# Capybara.net
KiCad netlist of a schematic drawn in Altium Designer
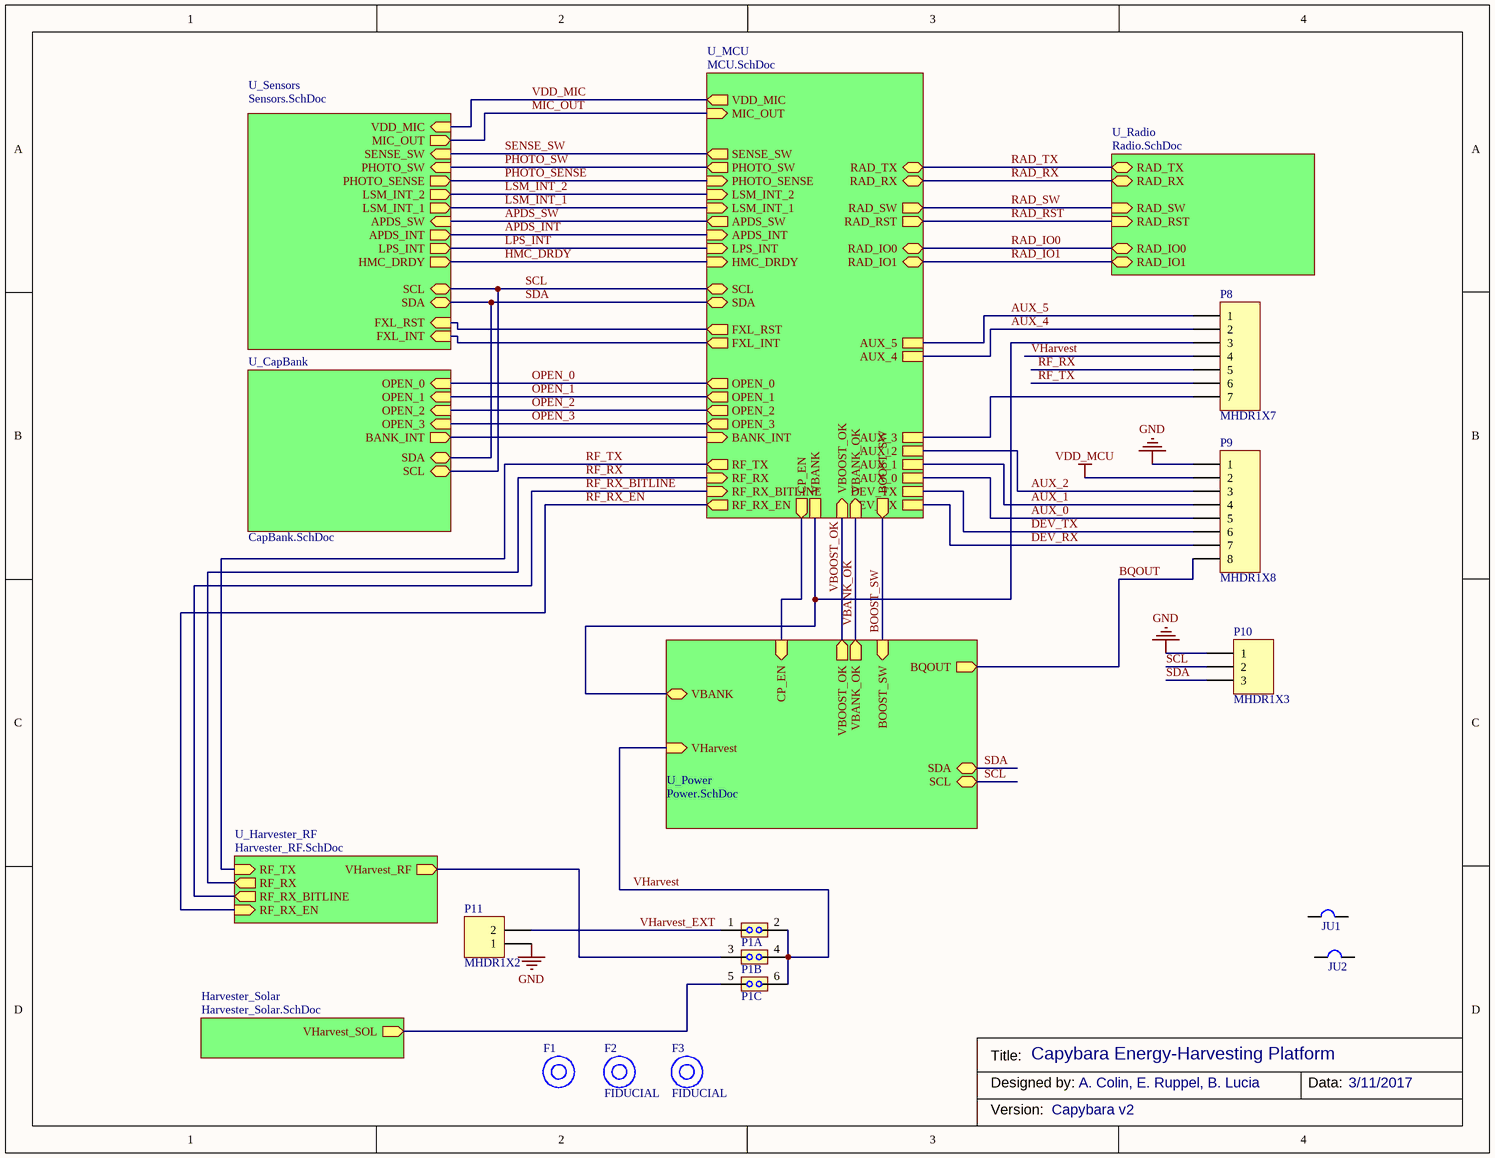
[diagram p0: Capybara.SchDoc]

(export (version "E")
  (design (tool "Eeschema 10.0.6"))
  (components
    (comp (ref "F1") (value "FIDUCIAL") (footprint "FIDUCIAL") (libsource (lib "Sprite") (part "FIDUCIAL")))
    (comp (ref "F2") (value "FIDUCIAL") (footprint "FIDUCIAL") (libsource (lib "Sprite") (part "FIDUCIAL")))
    (comp (ref "F3") (value "FIDUCIAL") (footprint "FIDUCIAL") (libsource (lib "Sprite") (part "FIDUCIAL")))
    (comp (ref "JU1") (value "JUMPER") (footprint "JUMPER0603") (libsource (lib "Sprite") (part "JUMPER")))
    (comp (ref "JU2") (value "JUMPER") (footprint "JUMPER0603") (libsource (lib "Sprite") (part "JUMPER")))
    (comp (ref "P1")
      (value "JMPHDR_12")
      (footprint "MHDR2X12")
      (fields
        (field (name "DIGI-KEY PART NUMBER") "S9015E-12-ND")
        (field (name "MANUFACTURER") "Sullins Connector Solutions")
        (field (name "MANUFACTURER PART NUMBER") "GRPB122VWVN-RC")
      )
      (libsource (lib "Sprite") (part "JMPHDR_12"))
    )
    (comp (ref "P8")
      (value "MHDR1X7")
      (footprint "MHDR1X7")
      (description "Header, 7-Pin")
      (fields
        (field (name "DIGI-KEY PART NUMBER") "952-3360-ND")
        (field (name "DISTRIBUTOR PART NUMBER") "855-M52-5000745")
        (field (name "PUBLISHER") "Altium Limited")
      )
      (libsource (lib "Miscellaneous Connectors") (part "MHDR1X7"))
    )
    (comp (ref "P9")
      (value "MHDR1X8")
      (footprint "MHDR1X8")
      (description "Header, 8-Pin")
      (fields
        (field (name "DIGI-KEY PART NUMBER") "952-3361-ND")
        (field (name "DISTRIBUTOR PART NUMBER") "855-M52-5000845")
        (field (name "PUBLISHER") "Altium Limited")
      )
      (libsource (lib "Miscellaneous Connectors") (part "MHDR1X8"))
    )
    (comp (ref "P10")
      (value "MHDR1X3")
      (footprint "MHDR1X3")
      (description "Header, 3-Pin")
      (fields
        (field (name "DIGI-KEY PART NUMBER") "952-3357-ND")
        (field (name "DISTRIBUTOR PART NUMBER") "855-M52-5000345")
        (field (name "PUBLISHER") "Altium Limited")
      )
      (libsource (lib "Miscellaneous Connectors") (part "MHDR1X3"))
    )
    (comp (ref "P11")
      (value "MHDR1X2")
      (footprint "MHDR1X2")
      (description "Header, 2-Pin")
      (fields
        (field (name "DIGI-KEY PART NUMBER") "SAM9931-ND")
        (field (name "MANUFACTURER") "Samtec Inc.")
        (field (name "PUBLISHER") "Altium Limited")
      )
      (libsource (lib "Miscellaneous Connectors") (part "MHDR1X2"))
    )
  )
  (nets
    (net (code "3") (name "/AUX_0") (class "Default")
      (node (ref "P9") (pin "5") (pinfunction "5_5") (pintype "passive"))
    )
    (net (code "4") (name "/AUX_1") (class "Default")
      (node (ref "P9") (pin "4") (pinfunction "4_4") (pintype "passive"))
    )
    (net (code "5") (name "/AUX_2") (class "Default")
      (node (ref "P9") (pin "3") (pinfunction "3_3") (pintype "passive"))
    )
    (net (code "6") (name "/AUX_3") (class "Default")
      (node (ref "P8") (pin "7") (pinfunction "7_7") (pintype "passive"))
    )
    (net (code "7") (name "/AUX_4") (class "Default")
      (node (ref "P8") (pin "2") (pinfunction "2_2") (pintype "passive"))
    )
    (net (code "8") (name "/AUX_5") (class "Default")
      (node (ref "P8") (pin "1") (pinfunction "1_1") (pintype "passive"))
    )
    (net (code "11") (name "/BQOUT") (class "Default")
      (node (ref "P9") (pin "8") (pinfunction "8_8") (pintype "passive"))
    )
    (net (code "13") (name "/DEV_RX") (class "Default")
      (node (ref "P9") (pin "7") (pinfunction "7_7") (pintype "passive"))
    )
    (net (code "14") (name "/DEV_TX") (class "Default")
      (node (ref "P9") (pin "6") (pinfunction "6_6") (pintype "passive"))
    )
    (net (code "34") (name "/RF_RX") (class "Default")
      (node (ref "P8") (pin "5") (pinfunction "5_5") (pintype "passive"))
    )
    (net (code "37") (name "/RF_TX") (class "Default")
      (node (ref "P8") (pin "6") (pinfunction "6_6") (pintype "passive"))
    )
    (net (code "38") (name "/SCL") (class "Default")
      (node (ref "P10") (pin "2") (pinfunction "2_2") (pintype "passive"))
    )
    (net (code "39") (name "/SDA") (class "Default")
      (node (ref "P10") (pin "3") (pinfunction "3_3") (pintype "passive"))
    )
    (net (code "41") (name "/VBANK") (class "Default")
      (node (ref "P8") (pin "3") (pinfunction "3_3") (pintype "passive"))
    )
    (net (code "45") (name "/VHarvest") (class "Default")
      (node (ref "P1") (pin "2") (pinfunction "2_2") (pintype "passive"))
      (node (ref "P1") (pin "4") (pinfunction "4_4") (pintype "passive"))
      (node (ref "P1") (pin "6") (pinfunction "6_6") (pintype "passive"))
      (node (ref "P8") (pin "4") (pinfunction "4_4") (pintype "passive"))
    )
    (net (code "46") (name "/VHarvest_EXT") (class "Default")
      (node (ref "P1") (pin "1") (pinfunction "1_1") (pintype "passive"))
      (node (ref "P11") (pin "2") (pinfunction "2_2") (pintype "passive"))
    )
    (net (code "47") (name "/VHarvest_RF") (class "Default")
      (node (ref "P1") (pin "3") (pinfunction "3_3") (pintype "passive"))
    )
    (net (code "48") (name "/VHarvest_SOL") (class "Default")
      (node (ref "P1") (pin "5") (pinfunction "5_5") (pintype "passive"))
    )
    (net (code "49") (name "GND") (class "Default")
      (node (ref "P10") (pin "1") (pinfunction "1_1") (pintype "passive"))
      (node (ref "P11") (pin "1") (pinfunction "1_1") (pintype "passive"))
      (node (ref "P9") (pin "1") (pinfunction "1_1") (pintype "passive"))
    )
    (net (code "50") (name "VDD_MCU") (class "Default")
      (node (ref "P9") (pin "2") (pinfunction "2_2") (pintype "passive"))
    )
    (net (code "51") (name "unconnected-(JU1-Pad1)") (class "Default")
      (node (ref "JU1") (pin "1") (pinfunction "1_1") (pintype "passive"))
    )
    (net (code "52") (name "unconnected-(JU1-Pad2)") (class "Default")
      (node (ref "JU1") (pin "2") (pinfunction "2_2") (pintype "passive"))
    )
    (net (code "53") (name "unconnected-(JU2-Pad1)") (class "Default")
      (node (ref "JU2") (pin "1") (pinfunction "1_1") (pintype "passive"))
    )
    (net (code "54") (name "unconnected-(JU2-Pad2)") (class "Default")
      (node (ref "JU2") (pin "2") (pinfunction "2_2") (pintype "passive"))
    )
  )
)
